# 8_-MODEM_MAIN.net
KiCad netlist of a schematic drawn in Altium Designer
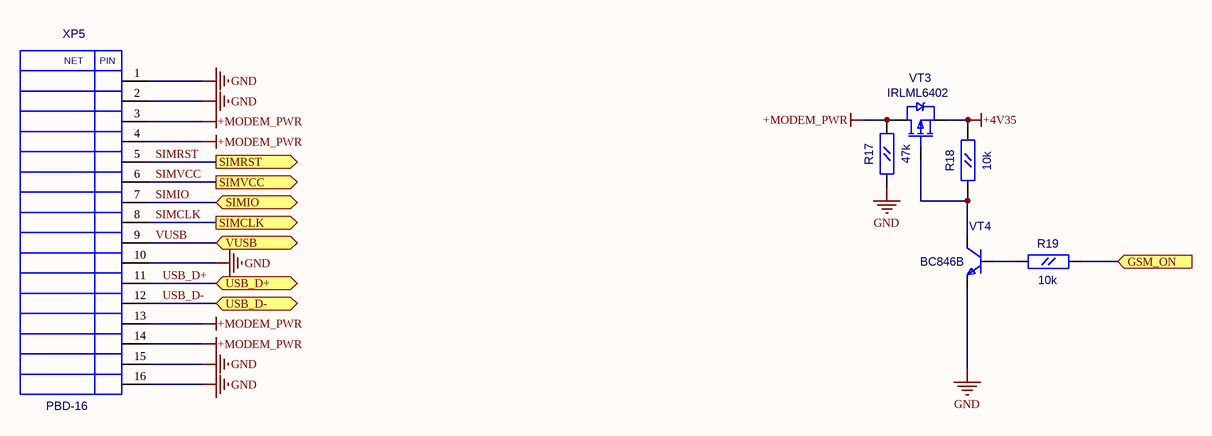
[diagram p0: [8]-MODEM_MAIN.SchDoc]

(export (version "E")
  (design (tool "Eeschema 10.0.6"))
  (components
    (comp (ref "R17")
      (value "47k")
      (footprint "RC0603")
      (description "RC0603")
      (libsource (lib "gprs_modem_2") (part "RC0603"))
    )
    (comp (ref "R18")
      (value "10k")
      (footprint "RC0603")
      (description "RC0603")
      (libsource (lib "gprs_modem_2") (part "RC0603"))
    )
    (comp (ref "R19")
      (value "10k")
      (footprint "RC0603")
      (description "RC0603")
      (libsource (lib "gprs_modem_2") (part "RC0603"))
    )
    (comp (ref "VT3")
      (value "IRLML6402")
      (footprint "SOT-23(123)")
      (description "HEXFET Power MOSFET")
      (libsource (lib "gprs_modem_2") (part "IRLML6402"))
    )
    (comp (ref "VT4")
      (value "BC846B")
      (footprint "SOT-23(123)")
      (description "BC846BLT1")
      (libsource (lib "gprs_modem_2") (part "BC846BLT1"))
    )
    (comp (ref "XP5") (value "PBD-16") (footprint "PBD16") (libsource (lib "fizik_lib") (part "PBD-16")))
  )
  (nets
    (net (code "1") (name "+4V35") (class "Default")
      (node (ref "R18") (pin "2") (pinfunction "B_2") (pintype "passive"))
      (node (ref "VT3") (pin "2") (pinfunction "S_2") (pintype "passive"))
    )
    (net (code "2") (name "+MODEM_PWR") (class "Default")
      (node (ref "R17") (pin "2") (pinfunction "B_2") (pintype "passive"))
      (node (ref "VT3") (pin "3") (pinfunction "D_3") (pintype "passive"))
      (node (ref "XP5") (pin "13") (pinfunction "13_13") (pintype "passive"))
      (node (ref "XP5") (pin "14") (pinfunction "14_14") (pintype "passive"))
      (node (ref "XP5") (pin "3") (pinfunction "3_3") (pintype "passive"))
      (node (ref "XP5") (pin "4") (pinfunction "4_4") (pintype "passive"))
    )
    (net (code "3") (name "/GSM_ON") (class "Default")
      (node (ref "R19") (pin "2") (pinfunction "B_2") (pintype "passive"))
    )
    (net (code "4") (name "/SIMCLK") (class "Default")
      (node (ref "XP5") (pin "8") (pinfunction "8_8") (pintype "passive"))
    )
    (net (code "5") (name "/SIMIO") (class "Default")
      (node (ref "XP5") (pin "7") (pinfunction "7_7") (pintype "passive"))
    )
    (net (code "6") (name "/SIMRST") (class "Default")
      (node (ref "XP5") (pin "5") (pinfunction "5_5") (pintype "passive"))
    )
    (net (code "7") (name "/SIMVCC") (class "Default")
      (node (ref "XP5") (pin "6") (pinfunction "6_6") (pintype "passive"))
    )
    (net (code "8") (name "/USB_D+") (class "Default")
      (node (ref "XP5") (pin "11") (pinfunction "11_11") (pintype "passive"))
    )
    (net (code "9") (name "/USB_D-") (class "Default")
      (node (ref "XP5") (pin "12") (pinfunction "12_12") (pintype "passive"))
    )
    (net (code "10") (name "/VUSB") (class "Default")
      (node (ref "XP5") (pin "9") (pinfunction "9_9") (pintype "passive"))
    )
    (net (code "11") (name "GND") (class "Default")
      (node (ref "R17") (pin "1") (pinfunction "A_1") (pintype "passive"))
      (node (ref "VT4") (pin "2") (pinfunction "E_2") (pintype "passive"))
      (node (ref "XP5") (pin "1") (pinfunction "1_1") (pintype "passive"))
      (node (ref "XP5") (pin "10") (pinfunction "10_10") (pintype "passive"))
      (node (ref "XP5") (pin "15") (pinfunction "15_15") (pintype "passive"))
      (node (ref "XP5") (pin "16") (pinfunction "16_16") (pintype "passive"))
      (node (ref "XP5") (pin "2") (pinfunction "2_2") (pintype "passive"))
    )
    (net (code "12") (name "Net-(R18-A)") (class "Default")
      (node (ref "R18") (pin "1") (pinfunction "A_1") (pintype "passive"))
      (node (ref "VT3") (pin "1") (pinfunction "G_1") (pintype "passive"))
      (node (ref "VT4") (pin "3") (pinfunction "C_3") (pintype "passive"))
    )
    (net (code "13") (name "Net-(R19-A)") (class "Default")
      (node (ref "R19") (pin "1") (pinfunction "A_1") (pintype "passive"))
      (node (ref "VT4") (pin "1") (pinfunction "B_1") (pintype "passive"))
    )
  )
)
